# Peripherals.net
KiCad netlist of a schematic drawn in Altium Designer
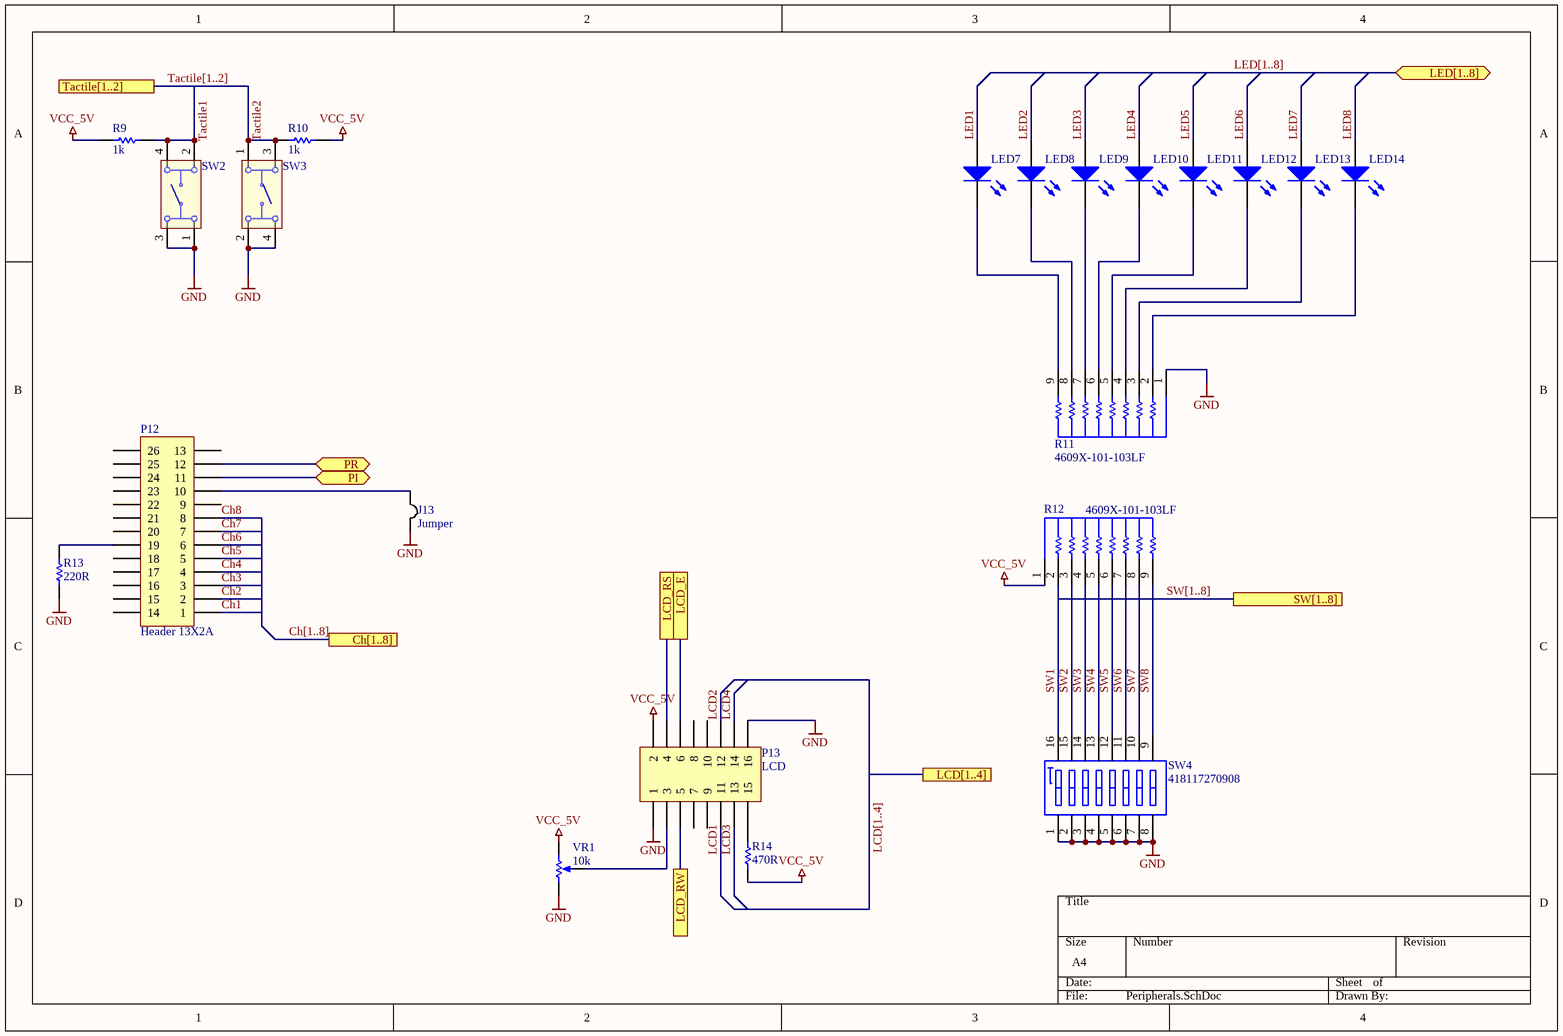
[diagram p0: Peripherals.SchDoc]

(export (version "E")
  (design (tool "Eeschema 10.0.6"))
  (components
    (comp (ref "J13")
      (value "Jumper")
      (footprint "SMDJumper")
      (libsource (lib "DS1E-S-DC3V") (part "Jumper"))
    )
    (comp (ref "LED7")
      (value "TX1")
      (footprint "Type 3mm")
      (description "THT LED round mono-color waterclear, WL-TMRW, Yellow")
      (fields (field (name "MANUFACTURER") "Wuerth Elektronik") (field (name "PARTNUMBER") "151033YS03000"))
      (libsource (lib "Altium Content Vault") (part "WE-LED_K1A2-2"))
    )
    (comp (ref "LED8")
      (value "TX1")
      (footprint "Type 3mm")
      (description "THT LED round mono-color waterclear, WL-TMRW, Yellow")
      (fields (field (name "MANUFACTURER") "Wuerth Elektronik") (field (name "PARTNUMBER") "151033YS03000"))
      (libsource (lib "Altium Content Vault") (part "WE-LED_K1A2-2"))
    )
    (comp (ref "LED9")
      (value "TX1")
      (footprint "Type 3mm")
      (description "THT LED round mono-color waterclear, WL-TMRW, Yellow")
      (fields (field (name "MANUFACTURER") "Wuerth Elektronik") (field (name "PARTNUMBER") "151033YS03000"))
      (libsource (lib "Altium Content Vault") (part "WE-LED_K1A2-2"))
    )
    (comp (ref "LED10")
      (value "TX1")
      (footprint "Type 3mm")
      (description "THT LED round mono-color waterclear, WL-TMRW, Yellow")
      (fields (field (name "MANUFACTURER") "Wuerth Elektronik") (field (name "PARTNUMBER") "151033YS03000"))
      (libsource (lib "Altium Content Vault") (part "WE-LED_K1A2-2"))
    )
    (comp (ref "LED11")
      (value "TX1")
      (footprint "Type 3mm")
      (description "THT LED round mono-color waterclear, WL-TMRW, Yellow")
      (fields (field (name "MANUFACTURER") "Wuerth Elektronik") (field (name "PARTNUMBER") "151033YS03000"))
      (libsource (lib "Altium Content Vault") (part "WE-LED_K1A2-2"))
    )
    (comp (ref "LED12")
      (value "TX1")
      (footprint "Type 3mm")
      (description "THT LED round mono-color waterclear, WL-TMRW, Yellow")
      (fields (field (name "MANUFACTURER") "Wuerth Elektronik") (field (name "PARTNUMBER") "151033YS03000"))
      (libsource (lib "Altium Content Vault") (part "WE-LED_K1A2-2"))
    )
    (comp (ref "LED13")
      (value "TX1")
      (footprint "Type 3mm")
      (description "THT LED round mono-color waterclear, WL-TMRW, Yellow")
      (fields (field (name "MANUFACTURER") "Wuerth Elektronik") (field (name "PARTNUMBER") "151033YS03000"))
      (libsource (lib "Altium Content Vault") (part "WE-LED_K1A2-2"))
    )
    (comp (ref "LED14")
      (value "TX1")
      (footprint "Type 3mm")
      (description "THT LED round mono-color waterclear, WL-TMRW, Yellow")
      (fields (field (name "MANUFACTURER") "Wuerth Elektronik") (field (name "PARTNUMBER") "151033YS03000"))
      (libsource (lib "Altium Content Vault") (part "WE-LED_K1A2-2"))
    )
    (comp (ref "P12")
      (value "Header 13X2A")
      (footprint "HDR2X13_CEN")
      (description "Header, 13-Pin, Dual row")
      (fields (field (name "PUBLISHER") "Altium Limited"))
      (libsource (lib "Miscellaneous Connectors") (part "Header 13X2A"))
    )
    (comp (ref "P13")
      (value "LCD")
      (footprint "HDR2X8")
      (description "Header, 8-Pin, Dual row")
      (fields (field (name "PUBLISHER") "Altium Limited"))
      (libsource (lib "Miscellaneous Connectors") (part "Header 8X2"))
    )
    (comp (ref "R9")
      (value "1k")
      (footprint "RESC0805(2012)_M")
      (description "1k 0.125W 1% 0805 (2012 Metric)  SMD")
      (fields (field (name "POWER") "0.125 W") (field (name "TOLERANCE") "1 %"))
      (libsource (lib "Altium Content Vault") (part "RES"))
    )
    (comp (ref "R10")
      (value "1k")
      (footprint "RESC0805(2012)_M")
      (description "1k 0.125W 1% 0805 (2012 Metric)  SMD")
      (fields (field (name "POWER") "0.125 W") (field (name "TOLERANCE") "1 %"))
      (libsource (lib "Altium Content Vault") (part "RES"))
    )
    (comp (ref "R11")
      (value "4609X-101-103LF")
      (footprint "BOUR-4609X")
      (description "Resistor, Network, 1.13 W, 10 kOhm, -55 to 125 degC, 9-Pin THD, RoHS, Bulk")
      (fields (field (name "TOLERANCE") "±2%") (field (name "MANUFACTURER") "Bourns"))
      (libsource (lib "Altium Content Vault") (part "RES-BUS-9"))
    )
    (comp (ref "R12")
      (value "4609X-101-103LF")
      (footprint "BOUR-4609X")
      (description "Resistor, Network, 1.13 W, 10 kOhm, -55 to 125 degC, 9-Pin THD, RoHS, Bulk")
      (fields (field (name "TOLERANCE") "±2%") (field (name "MANUFACTURER") "Bourns"))
      (libsource (lib "Altium Content Vault") (part "RES-BUS-9"))
    )
    (comp (ref "R13")
      (value "220R")
      (footprint "RESC0805(2012)_M")
      (description "220R 0.125W 1% 0805 (2012 Metric)  SMD")
      (fields (field (name "POWER") "0.125 W") (field (name "TOLERANCE") "1 %"))
      (libsource (lib "Altium Content Vault") (part "RES"))
    )
    (comp (ref "R14")
      (value "470R")
      (footprint "RESC0805(2012)_M")
      (description "470R 0.125W 1% 0805 (2012 Metric)  SMD")
      (fields (field (name "POWER") "0.125 W") (field (name "TOLERANCE") "1 %"))
      (libsource (lib "Altium Content Vault") (part "RES"))
    )
    (comp (ref "SW2")
      (value "430156130726")
      (footprint "430156130726")
      (description "WS-TATV THT Tact Switch 6X6 mm")
      (fields (field (name "MANUFACTURER") "Wuerth Elektronik"))
      (libsource (lib "Altium Content Vault") (part "WE-TACT-SW-4"))
    )
    (comp (ref "SW3")
      (value "430156130726")
      (footprint "430156130726")
      (description "WS-TATV THT Tact Switch 6X6 mm")
      (fields (field (name "MANUFACTURER") "Wuerth Elektronik"))
      (libsource (lib "") (part "WE-TACT-SW-4_1"))
    )
    (comp (ref "SW4")
      (value "418117270908")
      (footprint "418117270908")
      (description "WS-DITV 2.54 mm Compact THT Dip Switch with Raised Actuator")
      (fields (field (name "MANUFACTURER") "Wuerth Elektronik"))
      (libsource (lib "Altium Content Vault") (part "WE-DIP-SW-16"))
    )
    (comp (ref "VR1")
      (value "10k")
      (footprint "BOUR-3362P")
      (description "Square Trimpot(R) Trimming Potentiometer, 100 KOhm, 300 V, -55 to 125 degC, 3-Pin THD, RoHS, Tube")
      (fields (field (name "TOLERANCE") "1%"))
      (libsource (lib "Altium Content Vault") (part "RES-POT-3"))
    )
  )
  (nets
    (net (code "1") (name "/Ch1") (class "Default")
      (node (ref "P12") (pin "1") (pinfunction "1_1") (pintype "passive"))
    )
    (net (code "2") (name "/Ch2") (class "Default")
      (node (ref "P12") (pin "2") (pinfunction "2_2") (pintype "passive"))
    )
    (net (code "3") (name "/Ch3") (class "Default")
      (node (ref "P12") (pin "3") (pinfunction "3_3") (pintype "passive"))
    )
    (net (code "4") (name "/Ch4") (class "Default")
      (node (ref "P12") (pin "4") (pinfunction "4_4") (pintype "passive"))
    )
    (net (code "5") (name "/Ch5") (class "Default")
      (node (ref "P12") (pin "5") (pinfunction "5_5") (pintype "passive"))
    )
    (net (code "6") (name "/Ch6") (class "Default")
      (node (ref "P12") (pin "6") (pinfunction "6_6") (pintype "passive"))
    )
    (net (code "7") (name "/Ch7") (class "Default")
      (node (ref "P12") (pin "7") (pinfunction "7_7") (pintype "passive"))
    )
    (net (code "8") (name "/Ch8") (class "Default")
      (node (ref "P12") (pin "8") (pinfunction "8_8") (pintype "passive"))
    )
    (net (code "10") (name "/LCD1") (class "Default")
      (node (ref "P13") (pin "11") (pinfunction "11_11") (pintype "passive"))
    )
    (net (code "11") (name "/LCD2") (class "Default")
      (node (ref "P13") (pin "12") (pinfunction "12_12") (pintype "passive"))
    )
    (net (code "12") (name "/LCD3") (class "Default")
      (node (ref "P13") (pin "13") (pinfunction "13_13") (pintype "passive"))
    )
    (net (code "13") (name "/LCD4") (class "Default")
      (node (ref "P13") (pin "14") (pinfunction "14_14") (pintype "passive"))
    )
    (net (code "15") (name "/LCD_E") (class "Default")
      (node (ref "P13") (pin "6") (pinfunction "6_6") (pintype "passive"))
    )
    (net (code "16") (name "/LCD_RS") (class "Default")
      (node (ref "P13") (pin "4") (pinfunction "4_4") (pintype "passive"))
    )
    (net (code "17") (name "/LCD_RW") (class "Default")
      (node (ref "P13") (pin "5") (pinfunction "5_5") (pintype "passive"))
    )
    (net (code "18") (name "/LED1") (class "Default")
      (node (ref "LED7") (pin "2") (pinfunction "A_2") (pintype "passive"))
    )
    (net (code "19") (name "/LED2") (class "Default")
      (node (ref "LED8") (pin "2") (pinfunction "A_2") (pintype "passive"))
    )
    (net (code "20") (name "/LED3") (class "Default")
      (node (ref "LED9") (pin "2") (pinfunction "A_2") (pintype "passive"))
    )
    (net (code "21") (name "/LED4") (class "Default")
      (node (ref "LED10") (pin "2") (pinfunction "A_2") (pintype "passive"))
    )
    (net (code "22") (name "/LED5") (class "Default")
      (node (ref "LED11") (pin "2") (pinfunction "A_2") (pintype "passive"))
    )
    (net (code "23") (name "/LED6") (class "Default")
      (node (ref "LED12") (pin "2") (pinfunction "A_2") (pintype "passive"))
    )
    (net (code "24") (name "/LED7") (class "Default")
      (node (ref "LED13") (pin "2") (pinfunction "A_2") (pintype "passive"))
    )
    (net (code "25") (name "/LED8") (class "Default")
      (node (ref "LED14") (pin "2") (pinfunction "A_2") (pintype "passive"))
    )
    (net (code "27") (name "/PI") (class "Default")
      (node (ref "P12") (pin "11") (pinfunction "11_11") (pintype "passive"))
    )
    (net (code "28") (name "/PR") (class "Default")
      (node (ref "P12") (pin "12") (pinfunction "12_12") (pintype "passive"))
    )
    (net (code "29") (name "/SW1") (class "Default")
      (node (ref "R12") (pin "2") (pinfunction "2_2") (pintype "passive"))
      (node (ref "SW4") (pin "16") (pinfunction "16_16") (pintype "passive"))
    )
    (net (code "30") (name "/SW2") (class "Default")
      (node (ref "R12") (pin "3") (pinfunction "3_3") (pintype "passive"))
      (node (ref "SW4") (pin "15") (pinfunction "15_15") (pintype "passive"))
    )
    (net (code "31") (name "/SW3") (class "Default")
      (node (ref "R12") (pin "4") (pinfunction "4_4") (pintype "passive"))
      (node (ref "SW4") (pin "14") (pinfunction "14_14") (pintype "passive"))
    )
    (net (code "32") (name "/SW4") (class "Default")
      (node (ref "R12") (pin "5") (pinfunction "5_5") (pintype "passive"))
      (node (ref "SW4") (pin "13") (pinfunction "13_13") (pintype "passive"))
    )
    (net (code "33") (name "/SW5") (class "Default")
      (node (ref "R12") (pin "6") (pinfunction "6_6") (pintype "passive"))
      (node (ref "SW4") (pin "12") (pinfunction "12_12") (pintype "passive"))
    )
    (net (code "34") (name "/SW6") (class "Default")
      (node (ref "R12") (pin "7") (pinfunction "7_7") (pintype "passive"))
      (node (ref "SW4") (pin "11") (pinfunction "11_11") (pintype "passive"))
    )
    (net (code "35") (name "/SW7") (class "Default")
      (node (ref "R12") (pin "8") (pinfunction "8_8") (pintype "passive"))
      (node (ref "SW4") (pin "10") (pinfunction "10_10") (pintype "passive"))
    )
    (net (code "36") (name "/SW8") (class "Default")
      (node (ref "R12") (pin "9") (pinfunction "9_9") (pintype "passive"))
      (node (ref "SW4") (pin "9") (pinfunction "9_9") (pintype "passive"))
    )
    (net (code "38") (name "/Tactile1") (class "Default")
      (node (ref "R9") (pin "1") (pinfunction "1_1") (pintype "passive"))
      (node (ref "SW2") (pin "2") (pinfunction "2_2") (pintype "passive"))
      (node (ref "SW2") (pin "4") (pinfunction "4_4") (pintype "passive"))
    )
    (net (code "39") (name "/Tactile2") (class "Default")
      (node (ref "R10") (pin "2") (pinfunction "2_2") (pintype "passive"))
      (node (ref "SW3") (pin "1") (pinfunction "1_1") (pintype "passive"))
      (node (ref "SW3") (pin "3") (pinfunction "3_3") (pintype "passive"))
    )
    (net (code "41") (name "GND") (class "Default")
      (node (ref "J13") (pin "2") (pinfunction "2_2") (pintype "passive"))
      (node (ref "P13") (pin "1") (pinfunction "1_1") (pintype "passive"))
      (node (ref "P13") (pin "16") (pinfunction "16_16") (pintype "passive"))
      (node (ref "R11") (pin "1") (pinfunction "1_1") (pintype "passive"))
      (node (ref "R13") (pin "1") (pinfunction "1_1") (pintype "passive"))
      (node (ref "SW2") (pin "1") (pinfunction "1_1") (pintype "passive"))
      (node (ref "SW2") (pin "3") (pinfunction "3_3") (pintype "passive"))
      (node (ref "SW3") (pin "2") (pinfunction "2_2") (pintype "passive"))
      (node (ref "SW3") (pin "4") (pinfunction "4_4") (pintype "passive"))
      (node (ref "SW4") (pin "1") (pinfunction "1_1") (pintype "passive"))
      (node (ref "SW4") (pin "2") (pinfunction "2_2") (pintype "passive"))
      (node (ref "SW4") (pin "3") (pinfunction "3_3") (pintype "passive"))
      (node (ref "SW4") (pin "4") (pinfunction "4_4") (pintype "passive"))
      (node (ref "SW4") (pin "5") (pinfunction "5_5") (pintype "passive"))
      (node (ref "SW4") (pin "6") (pinfunction "6_6") (pintype "passive"))
      (node (ref "SW4") (pin "7") (pinfunction "7_7") (pintype "passive"))
      (node (ref "SW4") (pin "8") (pinfunction "8_8") (pintype "passive"))
      (node (ref "VR1") (pin "1") (pinfunction "CCW_1") (pintype "passive"))
    )
    (net (code "42") (name "Net-(J13-Pad1)") (class "Default")
      (node (ref "J13") (pin "1") (pinfunction "1_1") (pintype "passive"))
      (node (ref "P12") (pin "10") (pinfunction "10_10") (pintype "passive"))
    )
    (net (code "43") (name "Net-(LED7-K)") (class "Default")
      (node (ref "LED7") (pin "1") (pinfunction "K_1") (pintype "passive"))
      (node (ref "R11") (pin "9") (pinfunction "9_9") (pintype "passive"))
    )
    (net (code "44") (name "Net-(LED8-K)") (class "Default")
      (node (ref "LED8") (pin "1") (pinfunction "K_1") (pintype "passive"))
      (node (ref "R11") (pin "8") (pinfunction "8_8") (pintype "passive"))
    )
    (net (code "45") (name "Net-(LED9-K)") (class "Default")
      (node (ref "LED9") (pin "1") (pinfunction "K_1") (pintype "passive"))
      (node (ref "R11") (pin "7") (pinfunction "7_7") (pintype "passive"))
    )
    (net (code "46") (name "Net-(LED10-K)") (class "Default")
      (node (ref "LED10") (pin "1") (pinfunction "K_1") (pintype "passive"))
      (node (ref "R11") (pin "6") (pinfunction "6_6") (pintype "passive"))
    )
    (net (code "47") (name "Net-(LED11-K)") (class "Default")
      (node (ref "LED11") (pin "1") (pinfunction "K_1") (pintype "passive"))
      (node (ref "R11") (pin "5") (pinfunction "5_5") (pintype "passive"))
    )
    (net (code "48") (name "Net-(LED12-K)") (class "Default")
      (node (ref "LED12") (pin "1") (pinfunction "K_1") (pintype "passive"))
      (node (ref "R11") (pin "4") (pinfunction "4_4") (pintype "passive"))
    )
    (net (code "49") (name "Net-(LED13-K)") (class "Default")
      (node (ref "LED13") (pin "1") (pinfunction "K_1") (pintype "passive"))
      (node (ref "R11") (pin "3") (pinfunction "3_3") (pintype "passive"))
    )
    (net (code "50") (name "Net-(LED14-K)") (class "Default")
      (node (ref "LED14") (pin "1") (pinfunction "K_1") (pintype "passive"))
      (node (ref "R11") (pin "2") (pinfunction "2_2") (pintype "passive"))
    )
    (net (code "51") (name "Net-(P12-Pad19)") (class "Default")
      (node (ref "P12") (pin "19") (pinfunction "19_19") (pintype "passive"))
      (node (ref "R13") (pin "2") (pinfunction "2_2") (pintype "passive"))
    )
    (net (code "52") (name "Net-(P13-Pad15)") (class "Default")
      (node (ref "P13") (pin "15") (pinfunction "15_15") (pintype "passive"))
      (node (ref "R14") (pin "2") (pinfunction "2_2") (pintype "passive"))
    )
    (net (code "53") (name "Net-(VR1-S)") (class "Default")
      (node (ref "P13") (pin "3") (pinfunction "3_3") (pintype "passive"))
      (node (ref "VR1") (pin "2") (pinfunction "S_2") (pintype "passive"))
    )
    (net (code "54") (name "VCC_5V") (class "Default")
      (node (ref "P13") (pin "2") (pinfunction "2_2") (pintype "passive"))
      (node (ref "R10") (pin "1") (pinfunction "1_1") (pintype "passive"))
      (node (ref "R12") (pin "1") (pinfunction "1_1") (pintype "passive"))
      (node (ref "R14") (pin "1") (pinfunction "1_1") (pintype "passive"))
      (node (ref "R9") (pin "2") (pinfunction "2_2") (pintype "passive"))
      (node (ref "VR1") (pin "3") (pinfunction "CW_3") (pintype "passive"))
    )
    (net (code "55") (name "unconnected-(P12-Pad9)") (class "Default")
      (node (ref "P12") (pin "9") (pinfunction "9_9") (pintype "passive"))
    )
    (net (code "56") (name "unconnected-(P12-Pad13)") (class "Default")
      (node (ref "P12") (pin "13") (pinfunction "13_13") (pintype "passive"))
    )
    (net (code "57") (name "unconnected-(P12-Pad14)") (class "Default")
      (node (ref "P12") (pin "14") (pinfunction "14_14") (pintype "passive"))
    )
    (net (code "58") (name "unconnected-(P12-Pad15)") (class "Default")
      (node (ref "P12") (pin "15") (pinfunction "15_15") (pintype "passive"))
    )
    (net (code "59") (name "unconnected-(P12-Pad16)") (class "Default")
      (node (ref "P12") (pin "16") (pinfunction "16_16") (pintype "passive"))
    )
    (net (code "60") (name "unconnected-(P12-Pad17)") (class "Default")
      (node (ref "P12") (pin "17") (pinfunction "17_17") (pintype "passive"))
    )
    (net (code "61") (name "unconnected-(P12-Pad18)") (class "Default")
      (node (ref "P12") (pin "18") (pinfunction "18_18") (pintype "passive"))
    )
    (net (code "62") (name "unconnected-(P12-Pad20)") (class "Default")
      (node (ref "P12") (pin "20") (pinfunction "20_20") (pintype "passive"))
    )
    (net (code "63") (name "unconnected-(P12-Pad21)") (class "Default")
      (node (ref "P12") (pin "21") (pinfunction "21_21") (pintype "passive"))
    )
    (net (code "64") (name "unconnected-(P12-Pad22)") (class "Default")
      (node (ref "P12") (pin "22") (pinfunction "22_22") (pintype "passive"))
    )
    (net (code "65") (name "unconnected-(P12-Pad23)") (class "Default")
      (node (ref "P12") (pin "23") (pinfunction "23_23") (pintype "passive"))
    )
    (net (code "66") (name "unconnected-(P12-Pad24)") (class "Default")
      (node (ref "P12") (pin "24") (pinfunction "24_24") (pintype "passive"))
    )
    (net (code "67") (name "unconnected-(P12-Pad25)") (class "Default")
      (node (ref "P12") (pin "25") (pinfunction "25_25") (pintype "passive"))
    )
    (net (code "68") (name "unconnected-(P12-Pad26)") (class "Default")
      (node (ref "P12") (pin "26") (pinfunction "26_26") (pintype "passive"))
    )
    (net (code "69") (name "unconnected-(P13-Pad7)") (class "Default")
      (node (ref "P13") (pin "7") (pinfunction "7_7") (pintype "passive"))
    )
    (net (code "70") (name "unconnected-(P13-Pad8)") (class "Default")
      (node (ref "P13") (pin "8") (pinfunction "8_8") (pintype "passive"))
    )
    (net (code "71") (name "unconnected-(P13-Pad9)") (class "Default")
      (node (ref "P13") (pin "9") (pinfunction "9_9") (pintype "passive"))
    )
    (net (code "72") (name "unconnected-(P13-Pad10)") (class "Default")
      (node (ref "P13") (pin "10") (pinfunction "10_10") (pintype "passive"))
    )
  )
)
